# x-jalad_rev2.net
KiCad netlist of a schematic drawn in EAGLE
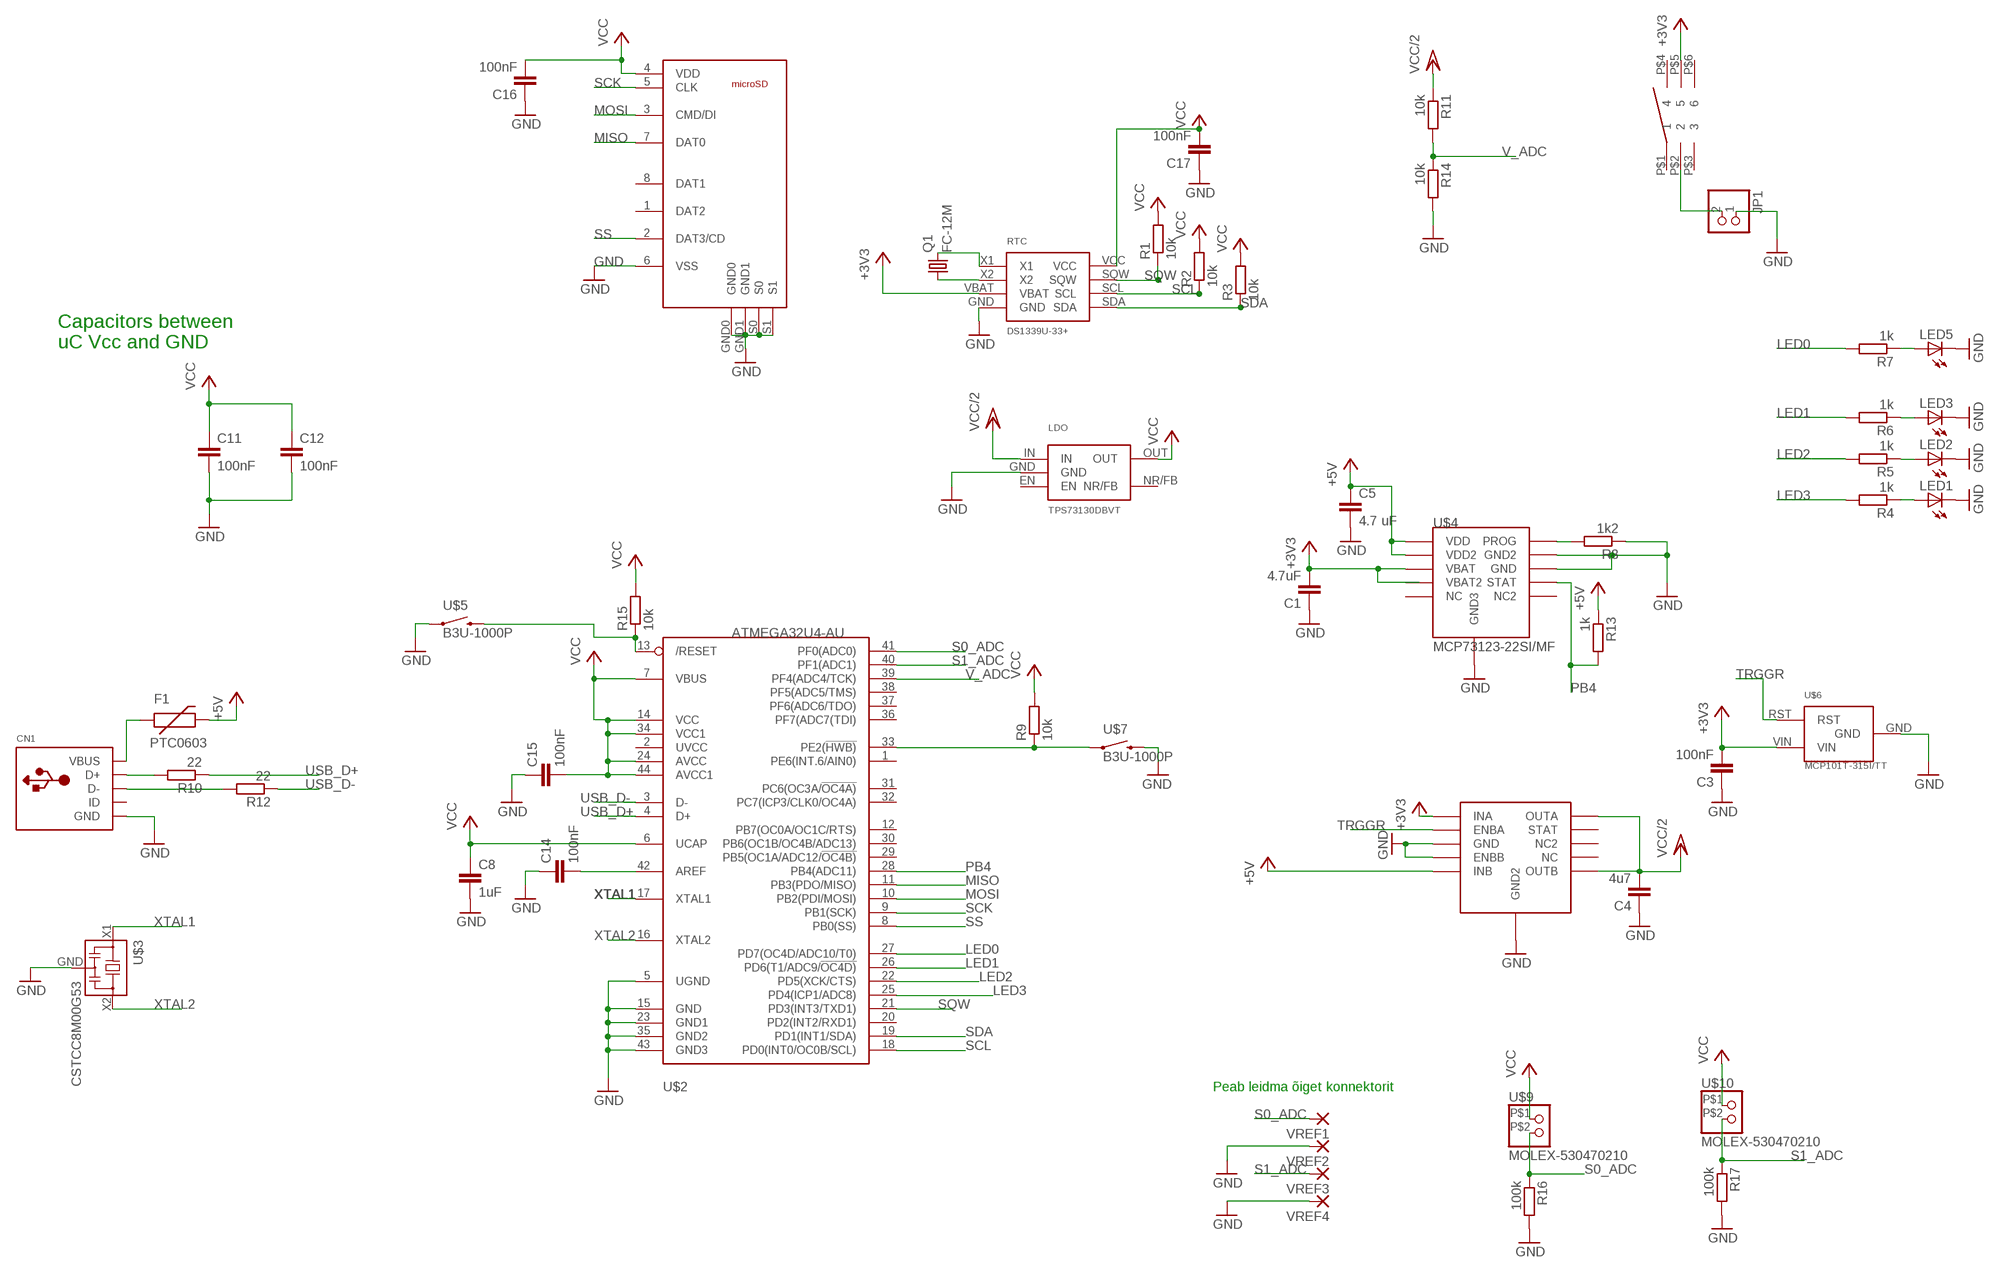
[diagram p0: schematic, sheet 1]

(export (version "E")
  (design (tool "Eeschema 10.0.6"))
  (components
    (comp (ref "2CH_IDEAL_DIODES")
      (value "LTC4413EDD-1")
      (footprint "eagle-import:DFN10")
      (libsource (lib "eagle-import") (part "LTC4413EDD-1"))
    )
    (comp (ref "C1")
      (value "4.7uF")
      (footprint "eagle-import:C0402")
      (libsource (lib "eagle-import") (part "CC0402"))
    )
    (comp (ref "C3")
      (value "100nF")
      (footprint "eagle-import:C0402")
      (libsource (lib "eagle-import") (part "CC0402"))
    )
    (comp (ref "C4")
      (value "4u7")
      (footprint "eagle-import:C0402")
      (libsource (lib "eagle-import") (part "CC0402"))
    )
    (comp (ref "C5")
      (value "4.7 uF")
      (footprint "eagle-import:C0603")
      (libsource (lib "eagle-import") (part "C-EUC0603"))
    )
    (comp (ref "C8")
      (value "1uF")
      (footprint "eagle-import:C0402")
      (libsource (lib "eagle-import") (part "CC0402"))
    )
    (comp (ref "C11")
      (value "100nF")
      (footprint "eagle-import:C0402")
      (libsource (lib "eagle-import") (part "CC0402"))
    )
    (comp (ref "C12")
      (value "100nF")
      (footprint "eagle-import:C0402")
      (libsource (lib "eagle-import") (part "CC0402"))
    )
    (comp (ref "C14")
      (value "100nF")
      (footprint "eagle-import:C0402")
      (libsource (lib "eagle-import") (part "CC0402"))
    )
    (comp (ref "C15")
      (value "100nF")
      (footprint "eagle-import:C0402")
      (libsource (lib "eagle-import") (part "CC0402"))
    )
    (comp (ref "C16")
      (value "100nF")
      (footprint "eagle-import:C0402")
      (libsource (lib "eagle-import") (part "CC0402"))
    )
    (comp (ref "C17")
      (value "100nF")
      (footprint "eagle-import:C0402")
      (libsource (lib "eagle-import") (part "CC0402"))
    )
    (comp (ref "CN1")
      (value "USBMINIB")
      (footprint "eagle-import:USB-MINIB")
      (libsource (lib "eagle-import") (part "USBMINIB"))
    )
    (comp (ref "F1")
      (value "PTC0603")
      (footprint "eagle-import:0603")
      (libsource (lib "eagle-import") (part "PTC0603"))
    )
    (comp (ref "JP1")
      (value "PINHD-1X2/90")
      (footprint "eagle-import:1X02_90")
      (libsource (lib "eagle-import") (part "PINHD-1X2/90"))
    )
    (comp (ref "LDO")
      (value "TPS73130DBVT")
      (footprint "eagle-import:SOT23-5")
      (libsource (lib "eagle-import") (part "TPS73130DBVT"))
    )
    (comp (ref "LED1")
      (value "LEDLD260")
      (footprint "eagle-import:LD260")
      (libsource (lib "eagle-import") (part "LEDLD260"))
    )
    (comp (ref "LED2")
      (value "LEDLD260")
      (footprint "eagle-import:LD260")
      (libsource (lib "eagle-import") (part "LEDLD260"))
    )
    (comp (ref "LED3")
      (value "LEDLD260")
      (footprint "eagle-import:LD260")
      (libsource (lib "eagle-import") (part "LEDLD260"))
    )
    (comp (ref "LED5")
      (value "LEDLD260")
      (footprint "eagle-import:LD260")
      (libsource (lib "eagle-import") (part "LEDLD260"))
    )
    (comp (ref "Q1")
      (value "FC-12M")
      (footprint "eagle-import:FC-12M")
      (libsource (lib "eagle-import") (part "FC-12M"))
    )
    (comp (ref "R1")
      (value "10k")
      (footprint "eagle-import:R0402")
      (libsource (lib "eagle-import") (part "RR0402"))
    )
    (comp (ref "R2")
      (value "10k")
      (footprint "eagle-import:R0402")
      (libsource (lib "eagle-import") (part "RR0402"))
    )
    (comp (ref "R3")
      (value "10k")
      (footprint "eagle-import:R0402")
      (libsource (lib "eagle-import") (part "RR0402"))
    )
    (comp (ref "R4")
      (value "1k")
      (footprint "eagle-import:R0402")
      (libsource (lib "eagle-import") (part "RR0402"))
    )
    (comp (ref "R5")
      (value "1k")
      (footprint "eagle-import:R0402")
      (libsource (lib "eagle-import") (part "RR0402"))
    )
    (comp (ref "R6")
      (value "1k")
      (footprint "eagle-import:R0402")
      (libsource (lib "eagle-import") (part "RR0402"))
    )
    (comp (ref "R7")
      (value "1k")
      (footprint "eagle-import:R0402")
      (libsource (lib "eagle-import") (part "RR0402"))
    )
    (comp (ref "R8")
      (value "1k2")
      (footprint "eagle-import:R0402")
      (libsource (lib "eagle-import") (part "RR0402"))
    )
    (comp (ref "R9")
      (value "10k")
      (footprint "eagle-import:R0402")
      (libsource (lib "eagle-import") (part "RR0402"))
    )
    (comp (ref "R10")
      (value "22")
      (footprint "eagle-import:R0402")
      (libsource (lib "eagle-import") (part "RR0402"))
    )
    (comp (ref "R11")
      (value "10k")
      (footprint "eagle-import:R0402")
      (libsource (lib "eagle-import") (part "RR0402"))
    )
    (comp (ref "R12")
      (value "22")
      (footprint "eagle-import:R0402")
      (libsource (lib "eagle-import") (part "RR0402"))
    )
    (comp (ref "R13")
      (value "1k")
      (footprint "eagle-import:R0402")
      (libsource (lib "eagle-import") (part "RR0402"))
    )
    (comp (ref "R14")
      (value "10k")
      (footprint "eagle-import:R0402")
      (libsource (lib "eagle-import") (part "RR0402"))
    )
    (comp (ref "R15")
      (value "10k")
      (footprint "eagle-import:R0402")
      (libsource (lib "eagle-import") (part "RR0402"))
    )
    (comp (ref "R16")
      (value "100k")
      (footprint "eagle-import:R0402")
      (libsource (lib "eagle-import") (part "RR0402"))
    )
    (comp (ref "R17")
      (value "100k")
      (footprint "eagle-import:R0402")
      (libsource (lib "eagle-import") (part "RR0402"))
    )
    (comp (ref "RTC")
      (value "DS1339U-33+")
      (footprint "eagle-import:MSOP8")
      (libsource (lib "eagle-import") (part "DS1339U-33+"))
    )
    (comp (ref "U$1")
      (value "MICROSD_HRS")
      (footprint "eagle-import:MICROSD_HRS")
      (libsource (lib "eagle-import") (part "MICROSD_HRS"))
    )
    (comp (ref "U$2")
      (value "ATMEGA32U4-AU")
      (footprint "eagle-import:TQFP44")
      (libsource (lib "eagle-import") (part "ATMEGA32U4-AU"))
    )
    (comp (ref "U$3")
      (value "CSTCC8M00G53")
      (footprint "eagle-import:SMDRESONATOR")
      (libsource (lib "eagle-import") (part "CSTCC8M00G53"))
    )
    (comp (ref "U$4")
      (value "MCP73123-22SI/MF")
      (footprint "eagle-import:DFN10")
      (libsource (lib "eagle-import") (part "MCP73123-22SI/MF"))
    )
    (comp (ref "U$5")
      (value "B3U-1000P")
      (footprint "eagle-import:SMD_BUTTON")
      (libsource (lib "eagle-import") (part "B3U-1000P"))
    )
    (comp (ref "U$6")
      (value "MCP101T-315I/TT")
      (footprint "eagle-import:SOT23-3")
      (libsource (lib "eagle-import") (part "MCP101T-315I/TT"))
    )
    (comp (ref "U$7")
      (value "B3U-1000P")
      (footprint "eagle-import:SMD_BUTTON")
      (libsource (lib "eagle-import") (part "B3U-1000P"))
    )
    (comp (ref "U$8")
      (value "SPPH410100")
      (footprint "eagle-import:SMD_LATCHING_BUTTON")
      (libsource (lib "eagle-import") (part "SPPH410100"))
    )
    (comp (ref "U$9")
      (value "MOLEX-530470210")
      (footprint "eagle-import:SMD_PINHEADER")
      (libsource (lib "eagle-import") (part "MOLEX-530470210"))
    )
    (comp (ref "U$10")
      (value "MOLEX-530470210")
      (footprint "eagle-import:SMD_PINHEADER")
      (libsource (lib "eagle-import") (part "MOLEX-530470210"))
    )
    (comp (ref "VREF1")
      (value "3,17/1,3")
      (footprint "eagle-import:3,17_1,3")
      (libsource (lib "eagle-import") (part "3,17/1,3"))
    )
    (comp (ref "VREF2")
      (value "3,17/1,3")
      (footprint "eagle-import:3,17_1,3")
      (libsource (lib "eagle-import") (part "3,17/1,3"))
    )
    (comp (ref "VREF3")
      (value "3,17/1,3")
      (footprint "eagle-import:3,17_1,3")
      (libsource (lib "eagle-import") (part "3,17/1,3"))
    )
    (comp (ref "VREF4")
      (value "3,17/1,3")
      (footprint "eagle-import:3,17_1,3")
      (libsource (lib "eagle-import") (part "3,17/1,3"))
    )
  )
  (nets
    (net (code "1") (name "+3V3") (class "Default")
      (node (ref "2CH_IDEAL_DIODES") (pin "INA") (pinfunction "INA_INA") (pintype "bidirectional"))
      (node (ref "C1") (pin "2") (pinfunction "2_2") (pintype "passive"))
      (node (ref "C3") (pin "2") (pinfunction "2_2") (pintype "passive"))
      (node (ref "RTC") (pin "VBAT") (pinfunction "VBAT_VBAT") (pintype "bidirectional"))
      (node (ref "U$4") (pin "VBAT") (pinfunction "VBAT_VBAT") (pintype "bidirectional"))
      (node (ref "U$6") (pin "VIN") (pinfunction "VIN_VIN") (pintype "bidirectional"))
      (node (ref "U$8") (pin "P$5") (pinfunction "5_P$5") (pintype "bidirectional"))
    )
    (net (code "2") (name "+5V") (class "Default")
      (node (ref "2CH_IDEAL_DIODES") (pin "INB") (pinfunction "INB_INB") (pintype "bidirectional"))
      (node (ref "C5") (pin "1") (pinfunction "1_1") (pintype "passive"))
      (node (ref "F1") (pin "2") (pinfunction "2_2") (pintype "bidirectional"))
      (node (ref "R13") (pin "1") (pinfunction "1_1") (pintype "passive"))
      (node (ref "U$4") (pin "VDD") (pinfunction "VDD_VDD") (pintype "bidirectional"))
      (node (ref "U$4") (pin "VDD2") (pinfunction "VDD2_VDD2") (pintype "bidirectional"))
    )
    (net (code "3") (name "/LED0") (class "Default")
      (node (ref "R7") (pin "2") (pinfunction "2_2") (pintype "passive"))
      (node (ref "U$2") (pin "27") (pinfunction "PD7(OC4D/ADC10/T0)_27") (pintype "bidirectional"))
    )
    (net (code "4") (name "/LED1") (class "Default")
      (node (ref "R6") (pin "2") (pinfunction "2_2") (pintype "passive"))
      (node (ref "U$2") (pin "26") (pinfunction "PD6(T1/ADC9/~{OC4D})_26") (pintype "bidirectional"))
    )
    (net (code "5") (name "/LED2") (class "Default")
      (node (ref "R5") (pin "2") (pinfunction "2_2") (pintype "passive"))
      (node (ref "U$2") (pin "22") (pinfunction "PD5(XCK/CTS)_22") (pintype "bidirectional"))
    )
    (net (code "6") (name "/LED3") (class "Default")
      (node (ref "R4") (pin "2") (pinfunction "2_2") (pintype "passive"))
      (node (ref "U$2") (pin "25") (pinfunction "PD4(ICP1/ADC8)_25") (pintype "bidirectional"))
    )
    (net (code "7") (name "/MISO") (class "Default")
      (node (ref "U$1") (pin "7") (pinfunction "DAT0_7") (pintype "bidirectional"))
      (node (ref "U$2") (pin "11") (pinfunction "PB3(PDO/MISO)_11") (pintype "bidirectional"))
    )
    (net (code "8") (name "/MOSI") (class "Default")
      (node (ref "U$1") (pin "3") (pinfunction "CMD/DI_3") (pintype "bidirectional"))
      (node (ref "U$2") (pin "10") (pinfunction "PB2(PDI/MOSI)_10") (pintype "bidirectional"))
    )
    (net (code "9") (name "/PB4") (class "Default")
      (node (ref "R13") (pin "2") (pinfunction "2_2") (pintype "passive"))
      (node (ref "U$2") (pin "28") (pinfunction "PB4(ADC11)_28") (pintype "bidirectional"))
      (node (ref "U$4") (pin "STAT") (pinfunction "STAT_STAT") (pintype "bidirectional"))
    )
    (net (code "10") (name "/S0_ADC") (class "Default")
      (node (ref "R16") (pin "1") (pinfunction "1_1") (pintype "passive"))
      (node (ref "U$2") (pin "41") (pinfunction "PF0(ADC0)_41") (pintype "bidirectional"))
      (node (ref "U$9") (pin "P$2") (pinfunction "2_P$2") (pintype "passive"))
      (node (ref "VREF1") (pin "1") (pinfunction "P_1") (pintype "passive"))
    )
    (net (code "11") (name "/S1_ADC") (class "Default")
      (node (ref "R17") (pin "1") (pinfunction "1_1") (pintype "passive"))
      (node (ref "U$10") (pin "P$2") (pinfunction "2_P$2") (pintype "passive"))
      (node (ref "U$2") (pin "40") (pinfunction "PF1(ADC1)_40") (pintype "bidirectional"))
      (node (ref "VREF3") (pin "1") (pinfunction "P_1") (pintype "passive"))
    )
    (net (code "12") (name "/SCK") (class "Default")
      (node (ref "U$1") (pin "5") (pinfunction "CLK_5") (pintype "bidirectional"))
      (node (ref "U$2") (pin "9") (pinfunction "PB1(SCK)_9") (pintype "bidirectional"))
    )
    (net (code "13") (name "/SCL") (class "Default")
      (node (ref "R2") (pin "1") (pinfunction "1_1") (pintype "passive"))
      (node (ref "RTC") (pin "SCL") (pinfunction "SCL_SCL") (pintype "bidirectional"))
      (node (ref "U$2") (pin "18") (pinfunction "PD0(INT0/OC0B/SCL)_18") (pintype "bidirectional"))
    )
    (net (code "14") (name "/SDA") (class "Default")
      (node (ref "R3") (pin "1") (pinfunction "1_1") (pintype "passive"))
      (node (ref "RTC") (pin "SDA") (pinfunction "SDA_SDA") (pintype "bidirectional"))
      (node (ref "U$2") (pin "19") (pinfunction "PD1(INT1/SDA)_19") (pintype "bidirectional"))
    )
    (net (code "15") (name "/SQW") (class "Default")
      (node (ref "R1") (pin "1") (pinfunction "1_1") (pintype "passive"))
      (node (ref "RTC") (pin "SQW") (pinfunction "SQW_SQW") (pintype "bidirectional"))
      (node (ref "U$2") (pin "21") (pinfunction "PD3(INT3/TXD1)_21") (pintype "bidirectional"))
    )
    (net (code "16") (name "/SS") (class "Default")
      (node (ref "U$1") (pin "2") (pinfunction "DAT3/CD_2") (pintype "bidirectional"))
      (node (ref "U$2") (pin "8") (pinfunction "PB0(SS)_8") (pintype "bidirectional"))
    )
    (net (code "17") (name "/TRGGR") (class "Default")
      (node (ref "2CH_IDEAL_DIODES") (pin "ENBA") (pinfunction "ENBA_ENBA") (pintype "bidirectional"))
      (node (ref "U$6") (pin "RST") (pinfunction "RST_RST") (pintype "bidirectional"))
    )
    (net (code "18") (name "/USB_D+") (class "Default")
      (node (ref "R10") (pin "1") (pinfunction "1_1") (pintype "passive"))
      (node (ref "U$2") (pin "4") (pinfunction "D+_4") (pintype "bidirectional"))
    )
    (net (code "19") (name "/USB_D-") (class "Default")
      (node (ref "R12") (pin "1") (pinfunction "1_1") (pintype "passive"))
      (node (ref "U$2") (pin "3") (pinfunction "D-_3") (pintype "bidirectional"))
    )
    (net (code "20") (name "/V_ADC") (class "Default")
      (node (ref "R11") (pin "2") (pinfunction "2_2") (pintype "passive"))
      (node (ref "R14") (pin "1") (pinfunction "1_1") (pintype "passive"))
      (node (ref "U$2") (pin "39") (pinfunction "PF4(ADC4/TCK)_39") (pintype "bidirectional"))
    )
    (net (code "21") (name "/XTAL1") (class "Default")
      (node (ref "U$2") (pin "17") (pinfunction "XTAL1_17") (pintype "bidirectional"))
      (node (ref "U$3") (pin "X1") (pinfunction "X1_X1") (pintype "passive"))
    )
    (net (code "22") (name "/XTAL2") (class "Default")
      (node (ref "U$2") (pin "16") (pinfunction "XTAL2_16") (pintype "bidirectional"))
      (node (ref "U$3") (pin "X2") (pinfunction "X2_X2") (pintype "passive"))
    )
    (net (code "23") (name "GND") (class "Default")
      (node (ref "2CH_IDEAL_DIODES") (pin "ENBB") (pinfunction "ENBB_ENBB") (pintype "bidirectional"))
      (node (ref "2CH_IDEAL_DIODES") (pin "GND") (pinfunction "GND_GND") (pintype "bidirectional"))
      (node (ref "2CH_IDEAL_DIODES") (pin "GND2") (pinfunction "GND2_GND2") (pintype "bidirectional"))
      (node (ref "C1") (pin "1") (pinfunction "1_1") (pintype "passive"))
      (node (ref "C11") (pin "2") (pinfunction "2_2") (pintype "passive"))
      (node (ref "C12") (pin "2") (pinfunction "2_2") (pintype "passive"))
      (node (ref "C14") (pin "1") (pinfunction "1_1") (pintype "passive"))
      (node (ref "C15") (pin "1") (pinfunction "1_1") (pintype "passive"))
      (node (ref "C16") (pin "1") (pinfunction "1_1") (pintype "passive"))
      (node (ref "C17") (pin "1") (pinfunction "1_1") (pintype "passive"))
      (node (ref "C3") (pin "1") (pinfunction "1_1") (pintype "passive"))
      (node (ref "C4") (pin "1") (pinfunction "1_1") (pintype "passive"))
      (node (ref "C5") (pin "2") (pinfunction "2_2") (pintype "passive"))
      (node (ref "C8") (pin "2") (pinfunction "2_2") (pintype "passive"))
      (node (ref "CN1") (pin "GND") (pinfunction "GND_GND") (pintype "power_in"))
      (node (ref "JP1") (pin "1") (pinfunction "1_1") (pintype "passive"))
      (node (ref "LDO") (pin "GND") (pinfunction "GND_GND") (pintype "bidirectional"))
      (node (ref "LED1") (pin "K") (pinfunction "C_K") (pintype "passive"))
      (node (ref "LED2") (pin "K") (pinfunction "C_K") (pintype "passive"))
      (node (ref "LED3") (pin "K") (pinfunction "C_K") (pintype "passive"))
      (node (ref "LED5") (pin "K") (pinfunction "C_K") (pintype "passive"))
      (node (ref "R14") (pin "2") (pinfunction "2_2") (pintype "passive"))
      (node (ref "R16") (pin "2") (pinfunction "2_2") (pintype "passive"))
      (node (ref "R17") (pin "2") (pinfunction "2_2") (pintype "passive"))
      (node (ref "R8") (pin "1") (pinfunction "1_1") (pintype "passive"))
      (node (ref "RTC") (pin "GND") (pinfunction "GND_GND") (pintype "bidirectional"))
      (node (ref "U$1") (pin "6") (pinfunction "VSS_6") (pintype "bidirectional"))
      (node (ref "U$1") (pin "GND0") (pinfunction "GND0_GND0") (pintype "bidirectional"))
      (node (ref "U$1") (pin "GND1") (pinfunction "GND1_GND1") (pintype "bidirectional"))
      (node (ref "U$1") (pin "S0") (pinfunction "S0_S0") (pintype "bidirectional"))
      (node (ref "U$1") (pin "S1") (pinfunction "S1_S1") (pintype "bidirectional"))
      (node (ref "U$2") (pin "15") (pinfunction "GND_15") (pintype "bidirectional"))
      (node (ref "U$2") (pin "23") (pinfunction "GND1_23") (pintype "bidirectional"))
      (node (ref "U$2") (pin "35") (pinfunction "GND2_35") (pintype "bidirectional"))
      (node (ref "U$2") (pin "43") (pinfunction "GND3_43") (pintype "bidirectional"))
      (node (ref "U$2") (pin "5") (pinfunction "UGND_5") (pintype "bidirectional"))
      (node (ref "U$3") (pin "GND") (pinfunction "GND_GND") (pintype "passive"))
      (node (ref "U$4") (pin "GND") (pinfunction "GND_GND") (pintype "bidirectional"))
      (node (ref "U$4") (pin "GND2") (pinfunction "GND2_GND2") (pintype "bidirectional"))
      (node (ref "U$4") (pin "GND3") (pinfunction "GND3_GND3") (pintype "bidirectional"))
      (node (ref "U$5") (pin "P$1") (pinfunction "1_P$1") (pintype "passive"))
      (node (ref "U$6") (pin "GND") (pinfunction "GND_GND") (pintype "bidirectional"))
      (node (ref "U$7") (pin "P$2") (pinfunction "2_P$2") (pintype "passive"))
      (node (ref "VREF2") (pin "1") (pinfunction "P_1") (pintype "passive"))
      (node (ref "VREF4") (pin "1") (pinfunction "P_1") (pintype "passive"))
    )
    (net (code "24") (name "Net-(CN1-PadD+)") (class "Default")
      (node (ref "CN1") (pin "D+") (pinfunction "D+_D+") (pintype "bidirectional"))
      (node (ref "R10") (pin "2") (pinfunction "2_2") (pintype "passive"))
    )
    (net (code "25") (name "Net-(CN1-PadD-)") (class "Default")
      (node (ref "CN1") (pin "D-") (pinfunction "D-_D-") (pintype "bidirectional"))
      (node (ref "R12") (pin "2") (pinfunction "2_2") (pintype "passive"))
    )
    (net (code "26") (name "Net-(CN1-PadVBUS)") (class "Default")
      (node (ref "CN1") (pin "VBUS") (pinfunction "VBUS_VBUS") (pintype "power_in"))
      (node (ref "F1") (pin "1") (pinfunction "1_1") (pintype "bidirectional"))
    )
    (net (code "27") (name "Net-(LED1-PadA)") (class "Default")
      (node (ref "LED1") (pin "A") (pinfunction "A_A") (pintype "passive"))
      (node (ref "R4") (pin "1") (pinfunction "1_1") (pintype "passive"))
    )
    (net (code "28") (name "Net-(LED2-PadA)") (class "Default")
      (node (ref "LED2") (pin "A") (pinfunction "A_A") (pintype "passive"))
      (node (ref "R5") (pin "1") (pinfunction "1_1") (pintype "passive"))
    )
    (net (code "29") (name "Net-(LED3-PadA)") (class "Default")
      (node (ref "LED3") (pin "A") (pinfunction "A_A") (pintype "passive"))
      (node (ref "R6") (pin "1") (pinfunction "1_1") (pintype "passive"))
    )
    (net (code "30") (name "Net-(LED5-PadA)") (class "Default")
      (node (ref "LED5") (pin "A") (pinfunction "A_A") (pintype "passive"))
      (node (ref "R7") (pin "1") (pinfunction "1_1") (pintype "passive"))
    )
    (net (code "31") (name "Net-(Q1-Pad1)") (class "Default")
      (node (ref "Q1") (pin "1") (pinfunction "1_1") (pintype "passive"))
      (node (ref "RTC") (pin "X2") (pinfunction "X2_X2") (pintype "bidirectional"))
    )
    (net (code "32") (name "Net-(Q1-Pad2)") (class "Default")
      (node (ref "Q1") (pin "2") (pinfunction "2_2") (pintype "passive"))
      (node (ref "RTC") (pin "X1") (pinfunction "X1_X1") (pintype "bidirectional"))
    )
    (net (code "33") (name "Net-(R8-Pad2)") (class "Default")
      (node (ref "R8") (pin "2") (pinfunction "2_2") (pintype "passive"))
      (node (ref "U$4") (pin "PROG") (pinfunction "PROG_PROG") (pintype "bidirectional"))
    )
    (net (code "34") (name "Net-(U$2-AREF)") (class "Default")
      (node (ref "C14") (pin "2") (pinfunction "2_2") (pintype "passive"))
      (node (ref "U$2") (pin "42") (pinfunction "AREF_42") (pintype "bidirectional"))
    )
    (net (code "35") (name "Net-(U$2-PE2(~{HWB}))") (class "Default")
      (node (ref "R9") (pin "1") (pinfunction "1_1") (pintype "passive"))
      (node (ref "U$2") (pin "33") (pinfunction "PE2(~{HWB})_33") (pintype "bidirectional"))
      (node (ref "U$7") (pin "P$1") (pinfunction "1_P$1") (pintype "passive"))
    )
    (net (code "36") (name "Net-(U$2-{slash}RESET)") (class "Default")
      (node (ref "R15") (pin "1") (pinfunction "1_1") (pintype "passive"))
      (node (ref "U$2") (pin "13") (pinfunction "/RESET_13") (pintype "bidirectional"))
      (node (ref "U$5") (pin "P$2") (pinfunction "2_P$2") (pintype "passive"))
    )
    (net (code "37") (name "Net-(U$8-2)") (class "Default")
      (node (ref "JP1") (pin "2") (pinfunction "2_2") (pintype "passive"))
      (node (ref "U$8") (pin "P$2") (pinfunction "2_P$2") (pintype "bidirectional"))
    )
    (net (code "38") (name "VCC") (class "Default")
      (node (ref "C11") (pin "1") (pinfunction "1_1") (pintype "passive"))
      (node (ref "C12") (pin "1") (pinfunction "1_1") (pintype "passive"))
      (node (ref "C15") (pin "2") (pinfunction "2_2") (pintype "passive"))
      (node (ref "C16") (pin "2") (pinfunction "2_2") (pintype "passive"))
      (node (ref "C17") (pin "2") (pinfunction "2_2") (pintype "passive"))
      (node (ref "C8") (pin "1") (pinfunction "1_1") (pintype "passive"))
      (node (ref "LDO") (pin "OUT") (pinfunction "OUT_OUT") (pintype "bidirectional"))
      (node (ref "R1") (pin "2") (pinfunction "2_2") (pintype "passive"))
      (node (ref "R15") (pin "2") (pinfunction "2_2") (pintype "passive"))
      (node (ref "R2") (pin "2") (pinfunction "2_2") (pintype "passive"))
      (node (ref "R3") (pin "2") (pinfunction "2_2") (pintype "passive"))
      (node (ref "R9") (pin "2") (pinfunction "2_2") (pintype "passive"))
      (node (ref "RTC") (pin "VCC") (pinfunction "VCC_VCC") (pintype "bidirectional"))
      (node (ref "U$1") (pin "4") (pinfunction "VDD_4") (pintype "bidirectional"))
      (node (ref "U$10") (pin "P$1") (pinfunction "1_P$1") (pintype "passive"))
      (node (ref "U$2") (pin "14") (pinfunction "VCC_14") (pintype "bidirectional"))
      (node (ref "U$2") (pin "24") (pinfunction "AVCC_24") (pintype "bidirectional"))
      (node (ref "U$2") (pin "34") (pinfunction "VCC1_34") (pintype "bidirectional"))
      (node (ref "U$2") (pin "44") (pinfunction "AVCC1_44") (pintype "bidirectional"))
      (node (ref "U$2") (pin "6") (pinfunction "UCAP_6") (pintype "bidirectional"))
      (node (ref "U$2") (pin "7") (pinfunction "VBUS_7") (pintype "bidirectional"))
      (node (ref "U$9") (pin "P$1") (pinfunction "1_P$1") (pintype "passive"))
    )
    (net (code "39") (name "VCC{slash}2") (class "Default")
      (node (ref "2CH_IDEAL_DIODES") (pin "OUTA") (pinfunction "OUTA_OUTA") (pintype "bidirectional"))
      (node (ref "2CH_IDEAL_DIODES") (pin "OUTB") (pinfunction "OUTB_OUTB") (pintype "bidirectional"))
      (node (ref "C4") (pin "2") (pinfunction "2_2") (pintype "passive"))
      (node (ref "LDO") (pin "IN") (pinfunction "IN_IN") (pintype "bidirectional"))
      (node (ref "R11") (pin "1") (pinfunction "1_1") (pintype "passive"))
    )
    (net (code "40") (name "unconnected-(2CH_IDEAL_DIODES-PadNC)") (class "Default")
      (node (ref "2CH_IDEAL_DIODES") (pin "NC") (pinfunction "NC_NC") (pintype "bidirectional"))
    )
    (net (code "41") (name "unconnected-(2CH_IDEAL_DIODES-PadNC2)") (class "Default")
      (node (ref "2CH_IDEAL_DIODES") (pin "NC2") (pinfunction "NC2_NC2") (pintype "bidirectional"))
    )
    (net (code "42") (name "unconnected-(2CH_IDEAL_DIODES-PadSTAT)") (class "Default")
      (node (ref "2CH_IDEAL_DIODES") (pin "STAT") (pinfunction "STAT_STAT") (pintype "bidirectional"))
    )
    (net (code "43") (name "unconnected-(CN1-PadID)") (class "Default")
      (node (ref "CN1") (pin "ID") (pinfunction "ID_ID") (pintype "bidirectional"))
    )
    (net (code "44") (name "unconnected-(LDO-PadEN)") (class "Default")
      (node (ref "LDO") (pin "EN") (pinfunction "EN_EN") (pintype "bidirectional"))
    )
    (net (code "45") (name "unconnected-(LDO-PadNR{slash}FB)") (class "Default")
      (node (ref "LDO") (pin "NR/FB") (pinfunction "NR/FB_NR/FB") (pintype "bidirectional"))
    )
    (net (code "46") (name "unconnected-(U$1-DAT1-Pad8)") (class "Default")
      (node (ref "U$1") (pin "8") (pinfunction "DAT1_8") (pintype "bidirectional"))
    )
    (net (code "47") (name "unconnected-(U$1-DAT2-Pad1)") (class "Default")
      (node (ref "U$1") (pin "1") (pinfunction "DAT2_1") (pintype "bidirectional"))
    )
    (net (code "48") (name "unconnected-(U$2-PB5(OC1A{slash}ADC12{slash}~{OC4B})-Pad29)") (class "Default")
      (node (ref "U$2") (pin "29") (pinfunction "PB5(OC1A/ADC12/~{OC4B})_29") (pintype "bidirectional"))
    )
    (net (code "49") (name "unconnected-(U$2-PB6(OC1B{slash}OC4B{slash}ADC13)-Pad30)") (class "Default")
      (node (ref "U$2") (pin "30") (pinfunction "PB6(OC1B/OC4B/ADC13)_30") (pintype "bidirectional"))
    )
    (net (code "50") (name "unconnected-(U$2-PB7(OC0A{slash}OC1C{slash}RTS)-Pad12)") (class "Default")
      (node (ref "U$2") (pin "12") (pinfunction "PB7(OC0A/OC1C/RTS)_12") (pintype "bidirectional"))
    )
    (net (code "51") (name "unconnected-(U$2-PC6(OC3A{slash}~{OC4A})-Pad31)") (class "Default")
      (node (ref "U$2") (pin "31") (pinfunction "PC6(OC3A/~{OC4A})_31") (pintype "bidirectional"))
    )
    (net (code "52") (name "unconnected-(U$2-PC7(ICP3{slash}CLK0{slash}OC4A)-Pad32)") (class "Default")
      (node (ref "U$2") (pin "32") (pinfunction "PC7(ICP3/CLK0/OC4A)_32") (pintype "bidirectional"))
    )
    (net (code "53") (name "unconnected-(U$2-PD2(INT2{slash}RXD1)-Pad20)") (class "Default")
      (node (ref "U$2") (pin "20") (pinfunction "PD2(INT2/RXD1)_20") (pintype "bidirectional"))
    )
    (net (code "54") (name "unconnected-(U$2-PE6(INT.6{slash}AIN0)-Pad1)") (class "Default")
      (node (ref "U$2") (pin "1") (pinfunction "PE6(INT.6/AIN0)_1") (pintype "bidirectional"))
    )
    (net (code "55") (name "unconnected-(U$2-PF5(ADC5{slash}TMS)-Pad38)") (class "Default")
      (node (ref "U$2") (pin "38") (pinfunction "PF5(ADC5/TMS)_38") (pintype "bidirectional"))
    )
    (net (code "56") (name "unconnected-(U$2-PF6(ADC6{slash}TDO)-Pad37)") (class "Default")
      (node (ref "U$2") (pin "37") (pinfunction "PF6(ADC6/TDO)_37") (pintype "bidirectional"))
    )
    (net (code "57") (name "unconnected-(U$2-PF7(ADC7(TDI)-Pad36)") (class "Default")
      (node (ref "U$2") (pin "36") (pinfunction "PF7(ADC7(TDI)_36") (pintype "bidirectional"))
    )
    (net (code "58") (name "unconnected-(U$2-UVCC-Pad2)") (class "Default")
      (node (ref "U$2") (pin "2") (pinfunction "UVCC_2") (pintype "bidirectional"))
    )
    (net (code "59") (name "unconnected-(U$4-PadNC)") (class "Default")
      (node (ref "U$4") (pin "NC") (pinfunction "NC_NC") (pintype "bidirectional"))
    )
    (net (code "60") (name "unconnected-(U$4-PadNC2)") (class "Default")
      (node (ref "U$4") (pin "NC2") (pinfunction "NC2_NC2") (pintype "bidirectional"))
    )
    (net (code "61") (name "unconnected-(U$4-PadVBAT2)") (class "Default")
      (node (ref "U$4") (pin "VBAT2") (pinfunction "VBAT2_VBAT2") (pintype "bidirectional"))
    )
    (net (code "62") (name "unconnected-(U$8-1-PadP$1)") (class "Default")
      (node (ref "U$8") (pin "P$1") (pinfunction "1_P$1") (pintype "bidirectional"))
    )
    (net (code "63") (name "unconnected-(U$8-3-PadP$3)") (class "Default")
      (node (ref "U$8") (pin "P$3") (pinfunction "3_P$3") (pintype "bidirectional"))
    )
    (net (code "64") (name "unconnected-(U$8-4-PadP$4)") (class "Default")
      (node (ref "U$8") (pin "P$4") (pinfunction "4_P$4") (pintype "bidirectional"))
    )
    (net (code "65") (name "unconnected-(U$8-6-PadP$6)") (class "Default")
      (node (ref "U$8") (pin "P$6") (pinfunction "6_P$6") (pintype "bidirectional"))
    )
  )
)
